# R7FA2E1A7_COG12864.net
KiCad netlist of a schematic drawn in EasyEDA Pro
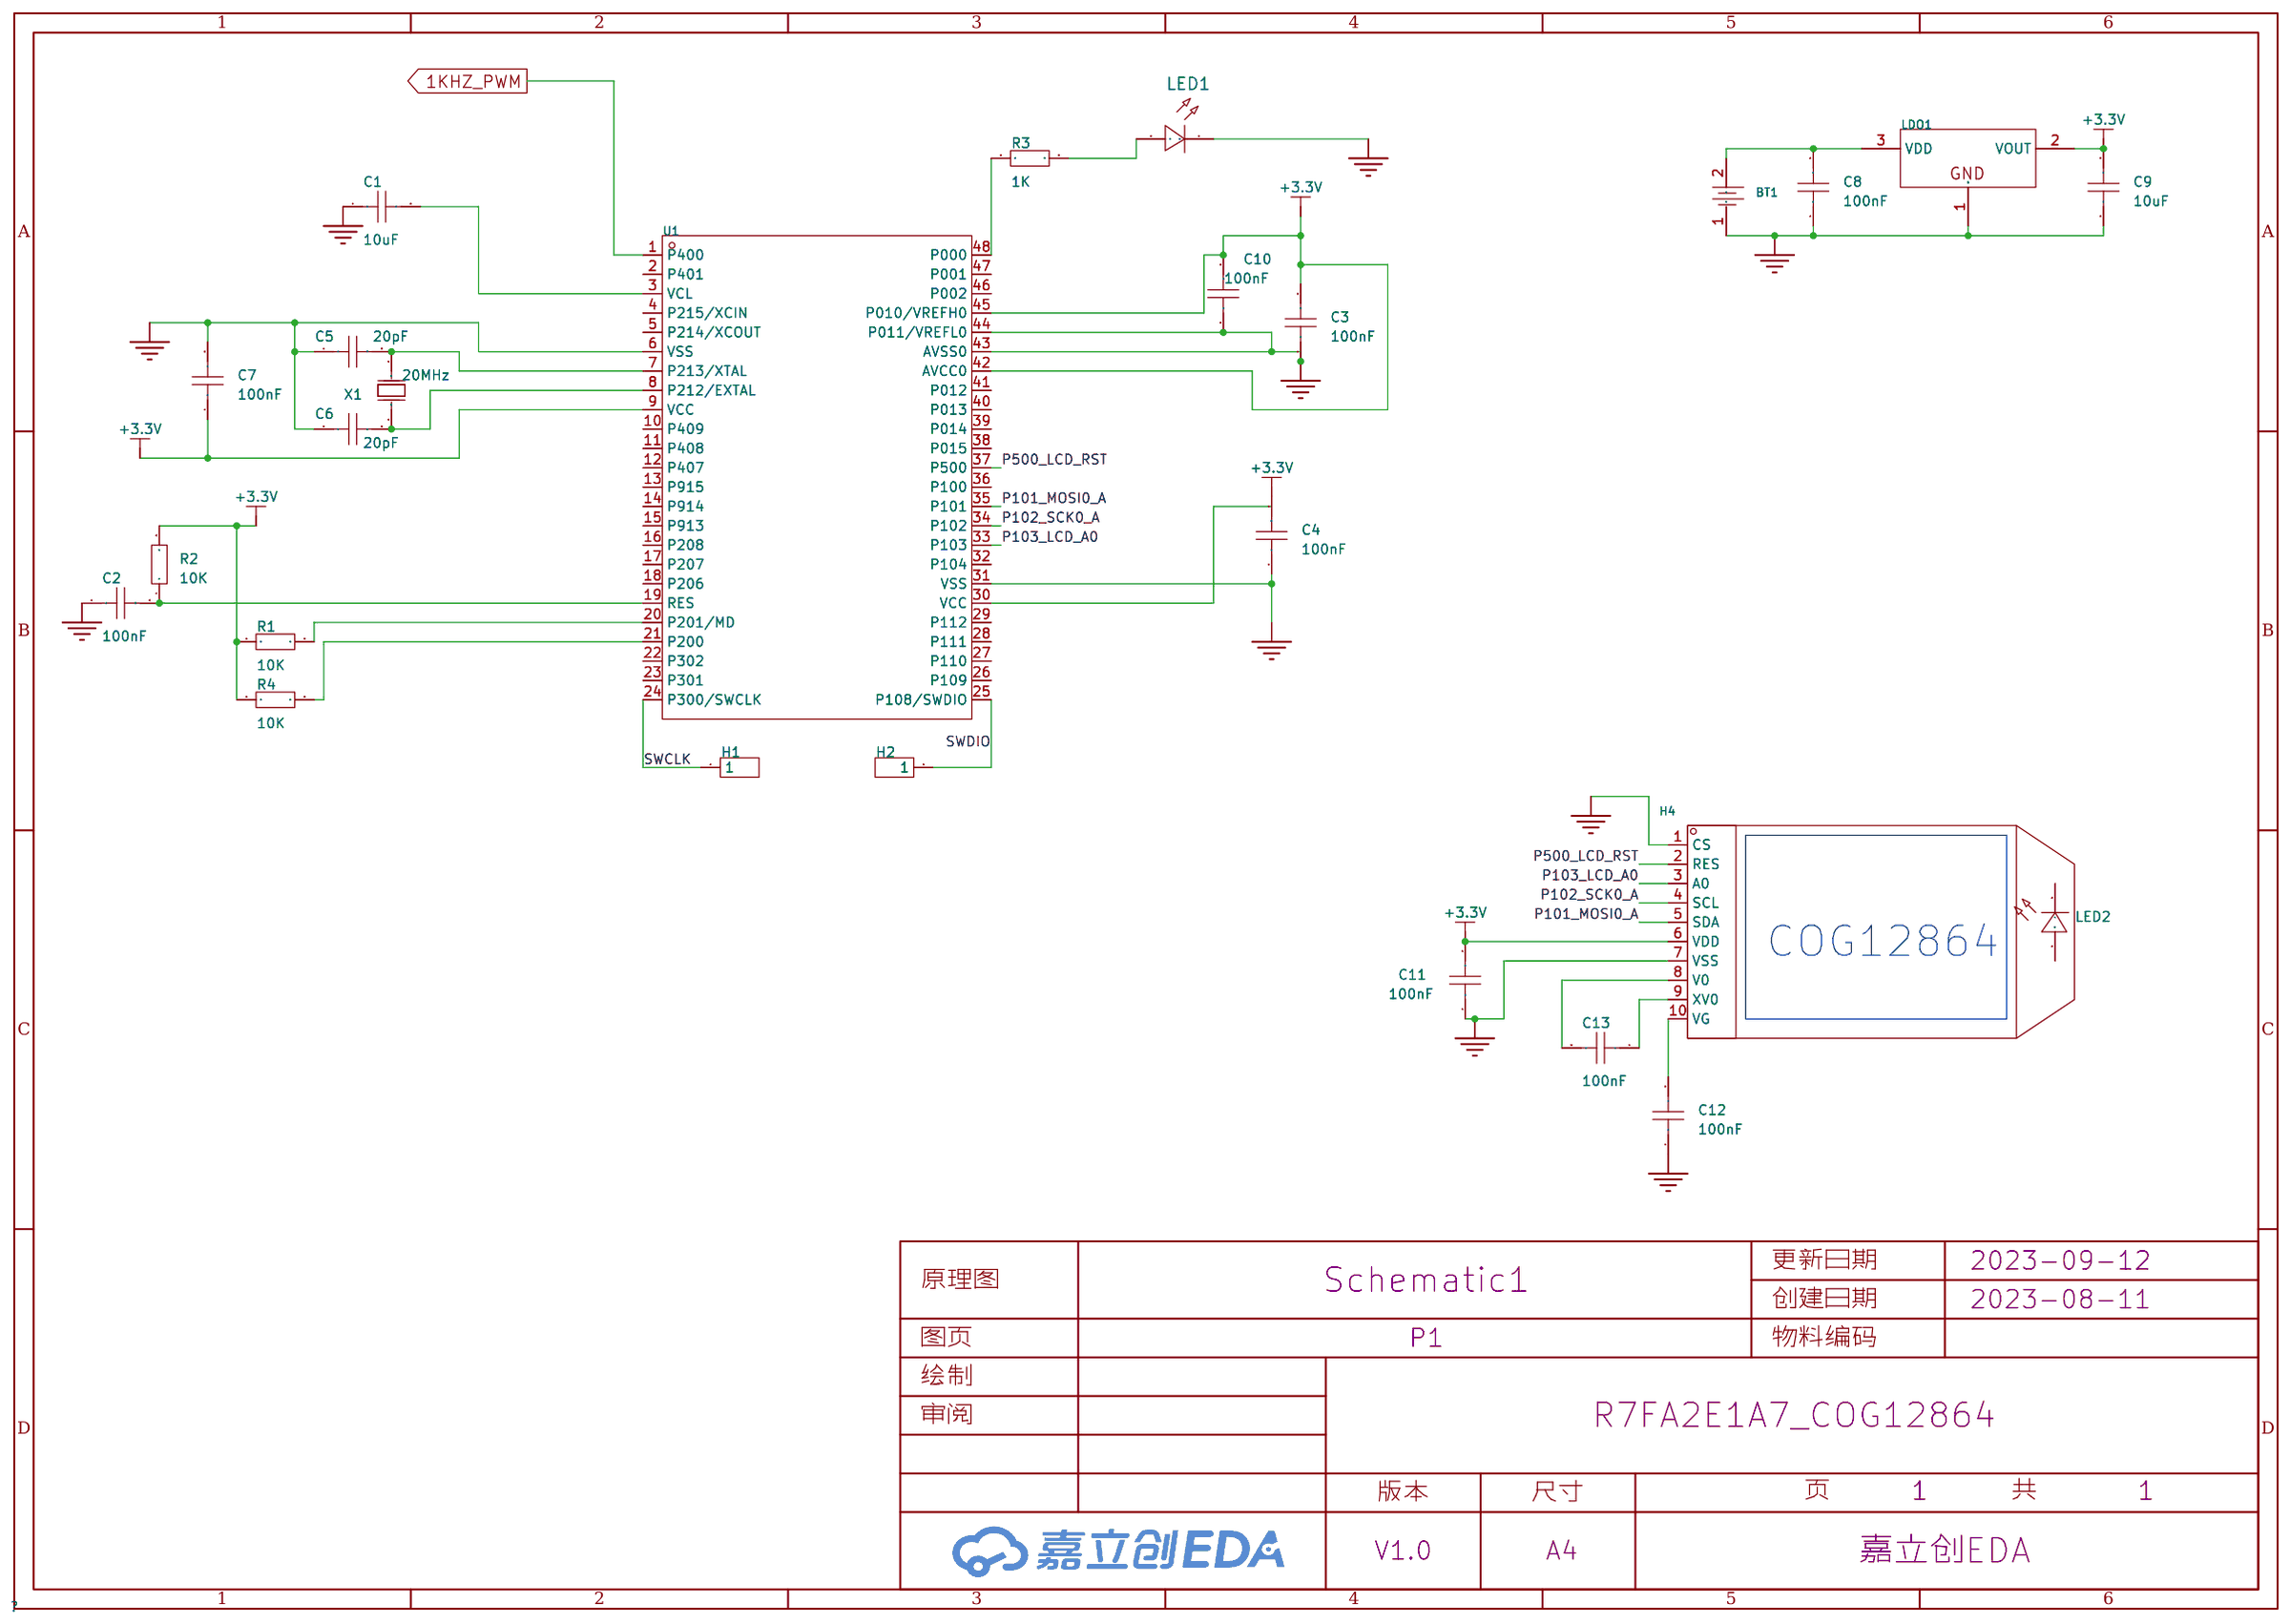
[diagram p0: schematic sheet]

(export (version "E")
  (design (tool "Eeschema 10.0.6"))
  (components
    (comp (ref "BT1")
      (value "BH-18650-B1BA002")
      (footprint "easyedapro:BATTERY-SMD_18650-1S-L77.1-W20.7-1")
      (description "连接器类型:电池盒;适用电池规格:18650;")
      (fields (field (name "Manufacturer") "MYOUNG(美阳)"))
      (libsource (lib "easyedapro") (part "BH-18650-B1BA002"))
    )
    (comp (ref "C1")
      (value "10uF")
      (footprint "easyedapro:C0603")
      (libsource (lib "easyedapro") (part "CapAcitance"))
    )
    (comp (ref "C2")
      (value "100nF")
      (footprint "easyedapro:C0603")
      (libsource (lib "easyedapro") (part "CapAcitance"))
    )
    (comp (ref "C3")
      (value "100nF")
      (footprint "easyedapro:C0603")
      (libsource (lib "easyedapro") (part "CapAcitance"))
    )
    (comp (ref "C4")
      (value "100nF")
      (footprint "easyedapro:C0603")
      (libsource (lib "easyedapro") (part "CapAcitance"))
    )
    (comp (ref "C5")
      (value "20pF")
      (footprint "easyedapro:C0603")
      (libsource (lib "easyedapro") (part "CapAcitance"))
    )
    (comp (ref "C6")
      (value "20pF")
      (footprint "easyedapro:C0603")
      (libsource (lib "easyedapro") (part "CapAcitance"))
    )
    (comp (ref "C7")
      (value "100nF")
      (footprint "easyedapro:C0603")
      (libsource (lib "easyedapro") (part "CapAcitance"))
    )
    (comp (ref "C8")
      (value "100nF")
      (footprint "easyedapro:C0603")
      (libsource (lib "easyedapro") (part "CapAcitance"))
    )
    (comp (ref "C9")
      (value "10uF")
      (footprint "easyedapro:C0603")
      (libsource (lib "easyedapro") (part "CapAcitance"))
    )
    (comp (ref "C10")
      (value "100nF")
      (footprint "easyedapro:C0603")
      (libsource (lib "easyedapro") (part "CapAcitance"))
    )
    (comp (ref "C11")
      (value "100nF")
      (footprint "easyedapro:C0603")
      (libsource (lib "easyedapro") (part "CapAcitance"))
    )
    (comp (ref "C12")
      (value "100nF")
      (footprint "easyedapro:C0603")
      (libsource (lib "easyedapro") (part "CapAcitance"))
    )
    (comp (ref "C13")
      (value "100nF")
      (footprint "easyedapro:C0603")
      (libsource (lib "easyedapro") (part "CapAcitance"))
    )
    (comp (ref "H1")
      (value "~")
      (footprint "easyedapro:HDR-TH_1P-V-M_XKB_X4611WV-01I-C28D40")
      (libsource (lib "easyedapro") (part "HDR_1x1"))
    )
    (comp (ref "H2")
      (value "~")
      (footprint "easyedapro:HDR-TH_1P-V-M_XKB_X4611WV-01I-C28D40")
      (libsource (lib "easyedapro") (part "HDR_1x1"))
    )
    (comp (ref "H4")
      (value "~")
      (footprint "easyedapro:HDR-TH_10P-P2.54-V-M-1")
      (fields (field (name "Manufacturer Part") "2.54-1*10P针") (field (name "Manufacturer") "BOOMELE(博穆精密)"))
      (libsource (lib "easyedapro") (part "Header-Male-2.54_1x10"))
    )
    (comp (ref "LDO1")
      (value "SC662K-3.3V")
      (footprint "easyedapro:SOT-23-3_L2.9-W1.3-P1.90-LS2.4-BR")
      (description "输出类型:固定;输出极性:正;最大输入电压:6V;输出电压:3.3V;输出电流:250mA;电源纹波抑制比(PSRR):50dB@(1kHz);")
      (fields (field (name "Manufacturer") "FM(富满)"))
      (libsource (lib "easyedapro") (part "SC662K-3.3V"))
    )
    (comp (ref "LED1")
      (value "~")
      (footprint "easyedapro:LED_0603")
      (libsource (lib "easyedapro") (part "LED_R"))
    )
    (comp (ref "LED2")
      (value "~")
      (footprint "easyedapro:LED_TH-3mm")
      (libsource (lib "easyedapro") (part "LED_TH-R"))
    )
    (comp (ref "R1") (value "10K") (footprint "easyedapro:R0603") (libsource (lib "easyedapro") (part "电阻")))
    (comp (ref "R2") (value "10K") (footprint "easyedapro:R0603") (libsource (lib "easyedapro") (part "电阻")))
    (comp (ref "R3") (value "1K") (footprint "easyedapro:R0603") (libsource (lib "easyedapro") (part "电阻")))
    (comp (ref "R4") (value "10K") (footprint "easyedapro:R0603") (libsource (lib "easyedapro") (part "电阻")))
    (comp (ref "U1")
      (value "R7FA2E1A72DFL#AA0")
      (footprint "easyedapro:LQFP-48_L7.0-W7.0-P0.50-LS9.0-BL")
      (description "CPU内核:ARM Cortex-M23;CPU最大主频:48MHz;工作电压范围:1.6V~5.5V;程序存储容量:64KB;RAM总容量:16KB;GPIO端口数量:40;")
      (fields (field (name "Manufacturer") "RENESAS(瑞萨)/IDT"))
      (libsource (lib "easyedapro") (part "R7FA2E1A72DFL#AA0"))
    )
    (comp (ref "X1")
      (value "20MHz")
      (footprint "easyedapro:OSC-TH_L10.0-W4.5-P5.00")
      (description "频率:20MHz;频率公差:±10ppm;负载电容:15pF;")
      (fields (field (name "Manufacturer Part") "X49SD20MPB2SC") (field (name "Manufacturer") "YXC(扬兴晶振)"))
      (libsource (lib "easyedapro") (part "X49SD20MPB2SC"))
    )
  )
  (nets
    (net (code "1") (name "+3.3V") (class "Default")
      (node (ref "C10") (pin "2") (pinfunction "2_2") (pintype "input"))
      (node (ref "C11") (pin "2") (pinfunction "2_2") (pintype "input"))
      (node (ref "C3") (pin "2") (pinfunction "2_2") (pintype "input"))
      (node (ref "C4") (pin "2") (pinfunction "2_2") (pintype "input"))
      (node (ref "C7") (pin "1") (pinfunction "1_1") (pintype "input"))
      (node (ref "C9") (pin "2") (pinfunction "2_2") (pintype "input"))
      (node (ref "H4") (pin "6") (pinfunction "VDD_6") (pintype "input"))
      (node (ref "LDO1") (pin "2") (pinfunction "VOUT_2") (pintype "input"))
      (node (ref "R1") (pin "1") (pinfunction "1_1") (pintype "input"))
      (node (ref "R2") (pin "2") (pinfunction "2_2") (pintype "input"))
      (node (ref "R4") (pin "1") (pinfunction "1_1") (pintype "input"))
      (node (ref "U1") (pin "42") (pinfunction "AVCC0_42") (pintype "input"))
      (node (ref "U1") (pin "45") (pinfunction "P010/VREFH0_45") (pintype "input"))
      (node (ref "U1") (pin "9") (pinfunction "VCC_9") (pintype "input"))
    )
    (net (code "2") (name "/P101_MOSI0_A") (class "Default")
      (node (ref "H4") (pin "5") (pinfunction "SDA_5") (pintype "input"))
      (node (ref "U1") (pin "35") (pinfunction "P101_35") (pintype "input"))
    )
    (net (code "3") (name "/P102_SCK0_A") (class "Default")
      (node (ref "H4") (pin "4") (pinfunction "SCL_4") (pintype "input"))
      (node (ref "U1") (pin "34") (pinfunction "P102_34") (pintype "input"))
    )
    (net (code "4") (name "/P103_LCD_A0") (class "Default")
      (node (ref "H4") (pin "3") (pinfunction "A0_3") (pintype "input"))
      (node (ref "U1") (pin "33") (pinfunction "P103_33") (pintype "input"))
    )
    (net (code "5") (name "/P500_LCD_RST") (class "Default")
      (node (ref "H4") (pin "2") (pinfunction "RES_2") (pintype "input"))
      (node (ref "U1") (pin "37") (pinfunction "P500_37") (pintype "input"))
    )
    (net (code "6") (name "/SWCLK") (class "Default")
      (node (ref "H1") (pin "1") (pinfunction "1_1") (pintype "unspecified"))
      (node (ref "U1") (pin "24") (pinfunction "P300/SWCLK_24") (pintype "input"))
    )
    (net (code "7") (name "/SWDIO") (class "Default")
      (node (ref "H2") (pin "1") (pinfunction "1_1") (pintype "unspecified"))
      (node (ref "U1") (pin "25") (pinfunction "P108/SWDIO_25") (pintype "input"))
    )
    (net (code "8") (name "1KHZ_PWM") (class "Default")
      (node (ref "U1") (pin "1") (pinfunction "P400_1") (pintype "input"))
    )
    (net (code "9") (name "GND") (class "Default")
      (node (ref "BT1") (pin "1") (pinfunction "1_1") (pintype "input"))
      (node (ref "C1") (pin "1") (pinfunction "1_1") (pintype "input"))
      (node (ref "C10") (pin "1") (pinfunction "1_1") (pintype "input"))
      (node (ref "C11") (pin "1") (pinfunction "1_1") (pintype "input"))
      (node (ref "C12") (pin "1") (pinfunction "1_1") (pintype "input"))
      (node (ref "C2") (pin "1") (pinfunction "1_1") (pintype "input"))
      (node (ref "C3") (pin "1") (pinfunction "1_1") (pintype "input"))
      (node (ref "C4") (pin "1") (pinfunction "1_1") (pintype "input"))
      (node (ref "C5") (pin "1") (pinfunction "1_1") (pintype "input"))
      (node (ref "C6") (pin "1") (pinfunction "1_1") (pintype "input"))
      (node (ref "C7") (pin "2") (pinfunction "2_2") (pintype "input"))
      (node (ref "C8") (pin "1") (pinfunction "1_1") (pintype "input"))
      (node (ref "C9") (pin "1") (pinfunction "1_1") (pintype "input"))
      (node (ref "H4") (pin "1") (pinfunction "CS_1") (pintype "input"))
      (node (ref "H4") (pin "7") (pinfunction "VSS_7") (pintype "input"))
      (node (ref "LDO1") (pin "1") (pinfunction "GND_1") (pintype "input"))
      (node (ref "LED1") (pin "1") (pinfunction "C_1") (pintype "input"))
      (node (ref "U1") (pin "31") (pinfunction "VSS_31") (pintype "input"))
      (node (ref "U1") (pin "43") (pinfunction "AVSS0_43") (pintype "input"))
      (node (ref "U1") (pin "44") (pinfunction "P011/VREFL0_44") (pintype "input"))
      (node (ref "U1") (pin "6") (pinfunction "VSS_6") (pintype "input"))
    )
    (net (code "10") (name "Net-(H4-V0)") (class "Default")
      (node (ref "C13") (pin "2") (pinfunction "2_2") (pintype "input"))
      (node (ref "H4") (pin "8") (pinfunction "V0_8") (pintype "input"))
    )
    (net (code "11") (name "Net-(H4-VG)") (class "Default")
      (node (ref "C12") (pin "2") (pinfunction "2_2") (pintype "input"))
      (node (ref "H4") (pin "10") (pinfunction "VG_10") (pintype "input"))
    )
    (net (code "12") (name "Net-(H4-XV0)") (class "Default")
      (node (ref "C13") (pin "1") (pinfunction "1_1") (pintype "input"))
      (node (ref "H4") (pin "9") (pinfunction "XV0_9") (pintype "input"))
    )
    (net (code "13") (name "Net-(LDO1-VDD)") (class "Default")
      (node (ref "BT1") (pin "2") (pinfunction "2_2") (pintype "input"))
      (node (ref "C8") (pin "2") (pinfunction "2_2") (pintype "input"))
      (node (ref "LDO1") (pin "3") (pinfunction "VDD_3") (pintype "input"))
    )
    (net (code "14") (name "Net-(LED1-A)") (class "Default")
      (node (ref "LED1") (pin "2") (pinfunction "A_2") (pintype "input"))
      (node (ref "R3") (pin "2") (pinfunction "2_2") (pintype "input"))
    )
    (net (code "15") (name "Net-(U1-P000)") (class "Default")
      (node (ref "R3") (pin "1") (pinfunction "1_1") (pintype "input"))
      (node (ref "U1") (pin "48") (pinfunction "P000_48") (pintype "input"))
    )
    (net (code "16") (name "Net-(U1-P200)") (class "Default")
      (node (ref "R4") (pin "2") (pinfunction "2_2") (pintype "input"))
      (node (ref "U1") (pin "21") (pinfunction "P200_21") (pintype "input"))
    )
    (net (code "17") (name "Net-(U1-P201{slash}MD)") (class "Default")
      (node (ref "R1") (pin "2") (pinfunction "2_2") (pintype "input"))
      (node (ref "U1") (pin "20") (pinfunction "P201/MD_20") (pintype "input"))
    )
    (net (code "18") (name "Net-(U1-P212{slash}EXTAL)") (class "Default")
      (node (ref "C6") (pin "2") (pinfunction "2_2") (pintype "input"))
      (node (ref "U1") (pin "8") (pinfunction "P212/EXTAL_8") (pintype "input"))
      (node (ref "X1") (pin "2") (pinfunction "OSC2_2") (pintype "input"))
    )
    (net (code "19") (name "Net-(U1-P213{slash}XTAL)") (class "Default")
      (node (ref "C5") (pin "2") (pinfunction "2_2") (pintype "input"))
      (node (ref "U1") (pin "7") (pinfunction "P213/XTAL_7") (pintype "input"))
      (node (ref "X1") (pin "1") (pinfunction "OSC1_1") (pintype "input"))
    )
    (net (code "20") (name "Net-(U1-RES)") (class "Default")
      (node (ref "C2") (pin "2") (pinfunction "2_2") (pintype "input"))
      (node (ref "R2") (pin "1") (pinfunction "1_1") (pintype "input"))
      (node (ref "U1") (pin "19") (pinfunction "RES_19") (pintype "input"))
    )
    (net (code "21") (name "Net-(U1-VCL)") (class "Default")
      (node (ref "C1") (pin "2") (pinfunction "2_2") (pintype "input"))
      (node (ref "U1") (pin "3") (pinfunction "VCL_3") (pintype "input"))
    )
    (net (code "22") (name "unconnected-(LED2-A-Pad2)") (class "Default")
      (node (ref "LED2") (pin "2") (pinfunction "A_2") (pintype "input"))
    )
    (net (code "23") (name "unconnected-(LED2-C-Pad1)") (class "Default")
      (node (ref "LED2") (pin "1") (pinfunction "C_1") (pintype "input"))
    )
    (net (code "24") (name "unconnected-(U1-P001-Pad47)") (class "Default")
      (node (ref "U1") (pin "47") (pinfunction "P001_47") (pintype "input"))
    )
    (net (code "25") (name "unconnected-(U1-P002-Pad46)") (class "Default")
      (node (ref "U1") (pin "46") (pinfunction "P002_46") (pintype "input"))
    )
    (net (code "26") (name "unconnected-(U1-P012-Pad41)") (class "Default")
      (node (ref "U1") (pin "41") (pinfunction "P012_41") (pintype "input"))
    )
    (net (code "27") (name "unconnected-(U1-P013-Pad40)") (class "Default")
      (node (ref "U1") (pin "40") (pinfunction "P013_40") (pintype "input"))
    )
    (net (code "28") (name "unconnected-(U1-P014-Pad39)") (class "Default")
      (node (ref "U1") (pin "39") (pinfunction "P014_39") (pintype "input"))
    )
    (net (code "29") (name "unconnected-(U1-P015-Pad38)") (class "Default")
      (node (ref "U1") (pin "38") (pinfunction "P015_38") (pintype "input"))
    )
    (net (code "30") (name "unconnected-(U1-P100-Pad36)") (class "Default")
      (node (ref "U1") (pin "36") (pinfunction "P100_36") (pintype "input"))
    )
    (net (code "31") (name "unconnected-(U1-P104-Pad32)") (class "Default")
      (node (ref "U1") (pin "32") (pinfunction "P104_32") (pintype "input"))
    )
    (net (code "32") (name "unconnected-(U1-P109-Pad26)") (class "Default")
      (node (ref "U1") (pin "26") (pinfunction "P109_26") (pintype "input"))
    )
    (net (code "33") (name "unconnected-(U1-P110-Pad27)") (class "Default")
      (node (ref "U1") (pin "27") (pinfunction "P110_27") (pintype "input"))
    )
    (net (code "34") (name "unconnected-(U1-P111-Pad28)") (class "Default")
      (node (ref "U1") (pin "28") (pinfunction "P111_28") (pintype "input"))
    )
    (net (code "35") (name "unconnected-(U1-P112-Pad29)") (class "Default")
      (node (ref "U1") (pin "29") (pinfunction "P112_29") (pintype "input"))
    )
    (net (code "36") (name "unconnected-(U1-P206-Pad18)") (class "Default")
      (node (ref "U1") (pin "18") (pinfunction "P206_18") (pintype "input"))
    )
    (net (code "37") (name "unconnected-(U1-P207-Pad17)") (class "Default")
      (node (ref "U1") (pin "17") (pinfunction "P207_17") (pintype "input"))
    )
    (net (code "38") (name "unconnected-(U1-P208-Pad16)") (class "Default")
      (node (ref "U1") (pin "16") (pinfunction "P208_16") (pintype "input"))
    )
    (net (code "39") (name "unconnected-(U1-P214{slash}XCOUT-Pad5)") (class "Default")
      (node (ref "U1") (pin "5") (pinfunction "P214/XCOUT_5") (pintype "input"))
    )
    (net (code "40") (name "unconnected-(U1-P215{slash}XCIN-Pad4)") (class "Default")
      (node (ref "U1") (pin "4") (pinfunction "P215/XCIN_4") (pintype "input"))
    )
    (net (code "41") (name "unconnected-(U1-P301-Pad23)") (class "Default")
      (node (ref "U1") (pin "23") (pinfunction "P301_23") (pintype "input"))
    )
    (net (code "42") (name "unconnected-(U1-P302-Pad22)") (class "Default")
      (node (ref "U1") (pin "22") (pinfunction "P302_22") (pintype "input"))
    )
    (net (code "43") (name "unconnected-(U1-P401-Pad2)") (class "Default")
      (node (ref "U1") (pin "2") (pinfunction "P401_2") (pintype "input"))
    )
    (net (code "44") (name "unconnected-(U1-P407-Pad12)") (class "Default")
      (node (ref "U1") (pin "12") (pinfunction "P407_12") (pintype "input"))
    )
    (net (code "45") (name "unconnected-(U1-P408-Pad11)") (class "Default")
      (node (ref "U1") (pin "11") (pinfunction "P408_11") (pintype "input"))
    )
    (net (code "46") (name "unconnected-(U1-P409-Pad10)") (class "Default")
      (node (ref "U1") (pin "10") (pinfunction "P409_10") (pintype "input"))
    )
    (net (code "47") (name "unconnected-(U1-P913-Pad15)") (class "Default")
      (node (ref "U1") (pin "15") (pinfunction "P913_15") (pintype "input"))
    )
    (net (code "48") (name "unconnected-(U1-P914-Pad14)") (class "Default")
      (node (ref "U1") (pin "14") (pinfunction "P914_14") (pintype "input"))
    )
    (net (code "49") (name "unconnected-(U1-P915-Pad13)") (class "Default")
      (node (ref "U1") (pin "13") (pinfunction "P915_13") (pintype "input"))
    )
    (net (code "50") (name "unconnected-(U1-VCC-Pad30)") (class "Default")
      (node (ref "U1") (pin "30") (pinfunction "VCC_30") (pintype "input"))
    )
  )
)
